# Serializer.net
KiCad netlist of a schematic drawn in Altium Designer
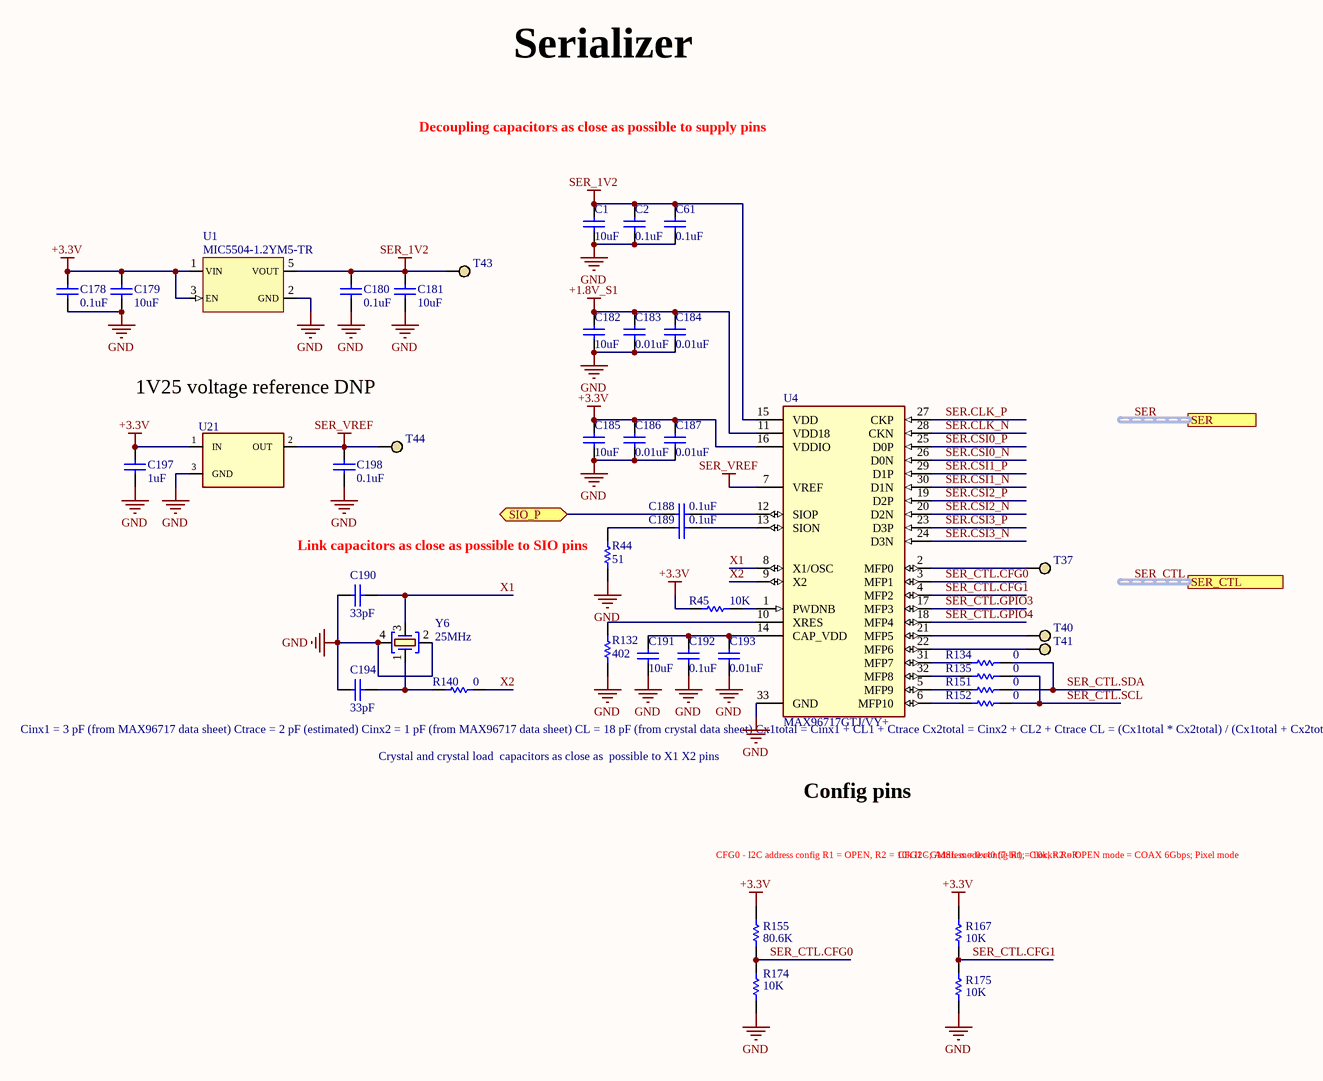
[diagram p0: Serializer.SchDoc]

(export (version "E")
  (design (tool "Eeschema 10.0.6"))
  (components
    (comp (ref "C1")
      (value "10uF")
      (footprint "CAPC1005X55USR")
      (description "CAP CER 10UF 10V X5R 0402")
      (fields
        (field (name "MANUFACTURER PART NUMBER") "CL05A106MP8NUB8")
        (field (name "MANUFACTURER") "Samsung Electro-Mechanics")
      )
      (libsource (lib "Radar FPGA RF") (part "CAP CER 10UF 10V X5R 0402"))
    )
    (comp (ref "C2")
      (value "0.1uF")
      (footprint "CAPC1005X55USR")
      (description "CAP CER 0.1UF 25V X5R 0402")
      (fields
        (field (name "MANUFACTURER PART NUMBER") "CL05A104KA5NNNC")
        (field (name "MANUFACTURER") "Samsung Electro-Mechanics")
      )
      (libsource (lib "Radar FPGA RF") (part "CAP CER 0.1UF 25V X5R 0402"))
    )
    (comp (ref "C61")
      (value "0.1uF")
      (footprint "CAPC1005X55USR")
      (description "CAP CER 0.1UF 25V X5R 0402")
      (fields
        (field (name "MANUFACTURER PART NUMBER") "CL05A104KA5NNNC")
        (field (name "MANUFACTURER") "Samsung Electro-Mechanics")
      )
      (libsource (lib "Radar FPGA RF") (part "CAP CER 0.1UF 25V X5R 0402"))
    )
    (comp (ref "C178")
      (value "0.1uF")
      (footprint "CAPC1005X55USR")
      (description "CAP CER 0.1UF 25V X7R 0402")
      (fields (field (name "MANUFACTURER") "AVX") (field (name "MANUFACTURER PART NUMBER") "04023C104KAT2A"))
      (libsource (lib "Signetik-passives") (part "0402C_0.1UF_25V_10%_X7R"))
    )
    (comp (ref "C179")
      (value "10uF")
      (footprint "CAPC1608X90N")
      (description "CAP CER 10UF 10V X5R 0603")
      (fields
        (field (name "MANUFACTURER") "Taiyo Yuden")
        (field (name "MANUFACTURER PART NUMBER") "LMK107BBJ106MALT")
      )
      (libsource (lib "Signetik-passives") (part "0603C_10UF_10V_20%_X5R"))
    )
    (comp (ref "C180")
      (value "0.1uF")
      (footprint "CAPC1005X55USR")
      (description "CAP CER 0.1UF 25V X7R 0402")
      (fields (field (name "MANUFACTURER") "AVX") (field (name "MANUFACTURER PART NUMBER") "04023C104KAT2A"))
      (libsource (lib "Signetik-passives") (part "0402C_0.1UF_25V_10%_X7R"))
    )
    (comp (ref "C181")
      (value "10uF")
      (footprint "CAPC1608X90N")
      (description "CAP CER 10UF 10V X5R 0603")
      (fields
        (field (name "MANUFACTURER") "Taiyo Yuden")
        (field (name "MANUFACTURER PART NUMBER") "LMK107BBJ106MALT")
      )
      (libsource (lib "Signetik-passives") (part "0603C_10UF_10V_20%_X5R"))
    )
    (comp (ref "C182")
      (value "10uF")
      (footprint "CAPC1005X55USR")
      (description "CAP CER 10UF 10V X5R 0402")
      (fields
        (field (name "MANUFACTURER PART NUMBER") "CL05A106MP8NUB8")
        (field (name "MANUFACTURER") "Samsung Electro-Mechanics")
      )
      (libsource (lib "Radar FPGA RF") (part "CAP CER 10UF 10V X5R 0402"))
    )
    (comp (ref "C183")
      (value "0.01uF")
      (footprint "CAPC1005X55USR")
      (description "CAP CER 10000PF 50V X7R 0402")
      (fields
        (field (name "MANUFACTURER PART NUMBER") "GCM155R71H103KA55D")
        (field (name "MANUFACTURER") "Murata Electronics")
      )
      (libsource (lib "Radar FPGA RF") (part "CAP CER 0.01uF 50V X7R 0402"))
    )
    (comp (ref "C184")
      (value "0.01uF")
      (footprint "CAPC1005X55USR")
      (description "CAP CER 10000PF 50V X7R 0402")
      (fields
        (field (name "MANUFACTURER PART NUMBER") "GCM155R71H103KA55D")
        (field (name "MANUFACTURER") "Murata Electronics")
      )
      (libsource (lib "Radar FPGA RF") (part "CAP CER 0.01uF 50V X7R 0402"))
    )
    (comp (ref "C185")
      (value "10uF")
      (footprint "CAPC1005X55USR")
      (description "CAP CER 10UF 10V X5R 0402")
      (fields
        (field (name "MANUFACTURER PART NUMBER") "CL05A106MP8NUB8")
        (field (name "MANUFACTURER") "Samsung Electro-Mechanics")
      )
      (libsource (lib "Radar FPGA RF") (part "CAP CER 10UF 10V X5R 0402"))
    )
    (comp (ref "C186")
      (value "0.01uF")
      (footprint "CAPC1005X55USR")
      (description "CAP CER 10000PF 50V X7R 0402")
      (fields
        (field (name "MANUFACTURER PART NUMBER") "GCM155R71H103KA55D")
        (field (name "MANUFACTURER") "Murata Electronics")
      )
      (libsource (lib "Radar FPGA RF") (part "CAP CER 0.01uF 50V X7R 0402"))
    )
    (comp (ref "C187")
      (value "0.01uF")
      (footprint "CAPC1005X55USR")
      (description "CAP CER 10000PF 50V X7R 0402")
      (fields
        (field (name "MANUFACTURER PART NUMBER") "GCM155R71H103KA55D")
        (field (name "MANUFACTURER") "Murata Electronics")
      )
      (libsource (lib "Radar FPGA RF") (part "CAP CER 0.01uF 50V X7R 0402"))
    )
    (comp (ref "C188")
      (value "0.1uF")
      (footprint "CAPC1005X55USR")
      (description "CAP CER 0.1UF 25V X5R 0402")
      (fields
        (field (name "MANUFACTURER PART NUMBER") "CL05A104KA5NNNC")
        (field (name "MANUFACTURER") "Samsung Electro-Mechanics")
      )
      (libsource (lib "Radar FPGA RF") (part "CAP CER 0.1UF 25V X5R 0402"))
    )
    (comp (ref "C189")
      (value "0.1uF")
      (footprint "CAPC1005X55USR")
      (description "CAP CER 0.1UF 25V X5R 0402")
      (fields
        (field (name "MANUFACTURER PART NUMBER") "CL05A104KA5NNNC")
        (field (name "MANUFACTURER") "Samsung Electro-Mechanics")
      )
      (libsource (lib "Radar FPGA RF") (part "CAP CER 0.1UF 25V X5R 0402"))
    )
    (comp (ref "C190")
      (value "33pF")
      (footprint "CAPC1005X55USR")
      (description "CAP CER 33PF 50V C0G/NP0 0402")
      (fields
        (field (name "MANUFACTURER PART NUMBER") "GRM1555C1H330JA01D")
        (field (name "MANUFACTURER") "Murata Electronics")
      )
      (libsource (lib "LL") (part "CAP CER 33PF 50V C0G/NP0 0402"))
    )
    (comp (ref "C191")
      (value "10uF")
      (footprint "CAPC1005X55USR")
      (description "CAP CER 10UF 10V X5R 0402")
      (fields
        (field (name "MANUFACTURER PART NUMBER") "CL05A106MP8NUB8")
        (field (name "MANUFACTURER") "Samsung Electro-Mechanics")
      )
      (libsource (lib "Radar FPGA RF") (part "CAP CER 10UF 10V X5R 0402"))
    )
    (comp (ref "C192")
      (value "0.1uF")
      (footprint "CAPC1005X55USR")
      (description "CAP CER 0.1UF 25V X5R 0402")
      (fields
        (field (name "MANUFACTURER PART NUMBER") "CL05A104KA5NNNC")
        (field (name "MANUFACTURER") "Samsung Electro-Mechanics")
      )
      (libsource (lib "Radar FPGA RF") (part "CAP CER 0.1UF 25V X5R 0402"))
    )
    (comp (ref "C193")
      (value "0.01uF")
      (footprint "CAPC1005X55USR")
      (description "CAP CER 10000PF 50V X7R 0402")
      (fields
        (field (name "MANUFACTURER PART NUMBER") "GCM155R71H103KA55D")
        (field (name "MANUFACTURER") "Murata Electronics")
      )
      (libsource (lib "Radar FPGA RF") (part "CAP CER 0.01uF 50V X7R 0402"))
    )
    (comp (ref "C194")
      (value "33pF")
      (footprint "CAPC1005X55USR")
      (description "CAP CER 33PF 50V C0G/NP0 0402")
      (fields
        (field (name "MANUFACTURER PART NUMBER") "GRM1555C1H330JA01D")
        (field (name "MANUFACTURER") "Murata Electronics")
      )
      (libsource (lib "LL") (part "CAP CER 33PF 50V C0G/NP0 0402"))
    )
    (comp (ref "C197")
      (value "1uF")
      (footprint "CAPC1005X55USR")
      (description "CAP CER 1UF 10V X5R 0402")
      (fields
        (field (name "MANUFACTURER PART NUMBER") "CL05A105MP5NNNC")
        (field (name "MANUFACTURER") "Samsung Electro-Mechanics")
      )
      (libsource (lib "LL") (part "CAP CER 1UF 10V X5R 0402"))
    )
    (comp (ref "C198")
      (value "0.1uF")
      (footprint "CAPC1005X55USR")
      (description "CAP CER 0.1UF 25V X7R 0402")
      (fields (field (name "MANUFACTURER") "AVX") (field (name "MANUFACTURER PART NUMBER") "04023C104KAT2A"))
      (libsource (lib "Signetik-passives") (part "0402C_0.1UF_25V_10%_X7R"))
    )
    (comp (ref "R44")
      (value "51")
      (footprint "RESC1005X40USR")
      (description "RES 51 OHM 1% 1/16W 0402")
      (fields
        (field (name "MANUFACTURER PART NUMBER") "RC0402FR-0751RL")
        (field (name "MANUFACTURER") "YAGEO")
      )
      (libsource (lib "LL") (part "RES 51 OHM 1% 1/16W 0402"))
    )
    (comp (ref "R45")
      (value "10K")
      (footprint "RESC1005X40USR")
      (description "RES 10K OHM 1% 1/16W 0402")
      (fields
        (field (name "MANUFACTURER") "YAGEO")
        (field (name "MANUFACTURER PART NUMBER") "RC0402FR-0710KL")
      )
      (libsource (lib "Radar FPGA RF") (part "RES 10K OHM 1% 1/16W 0402"))
    )
    (comp (ref "R132")
      (value "402")
      (footprint "RESC1005X40USR")
      (description "RES 402 OHM 1% 1/16W 0402")
      (fields
        (field (name "MANUFACTURER PART NUMBER") "RC0402FR-07402RL")
        (field (name "MANUFACTURER") "YAGEO")
      )
      (libsource (lib "LL") (part "RES 402 OHM 1% 1/16W 0402"))
    )
    (comp (ref "R134")
      (value "0")
      (footprint "RESC1005X40USR")
      (description "RES 0 OHM JUMPER 1/16W 0402")
      (fields
        (field (name "MANUFACTURER") "Yageo")
        (field (name "MANUFACTURER PART NUMBER") "RC0402JR-070RL")
      )
      (libsource (lib "Radar FPGA RF") (part "RES 0 OHM JUMPER 1/16W 0402"))
    )
    (comp (ref "R135")
      (value "0")
      (footprint "RESC1005X40USR")
      (description "RES 0 OHM JUMPER 1/16W 0402")
      (fields
        (field (name "MANUFACTURER") "Yageo")
        (field (name "MANUFACTURER PART NUMBER") "RC0402JR-070RL")
      )
      (libsource (lib "Radar FPGA RF") (part "RES 0 OHM JUMPER 1/16W 0402"))
    )
    (comp (ref "R140")
      (value "0")
      (footprint "RESC1005X40USR")
      (description "RES 0 OHM JUMPER 1/16W 0402")
      (fields
        (field (name "MANUFACTURER") "Yageo")
        (field (name "MANUFACTURER PART NUMBER") "RC0402JR-070RL")
      )
      (libsource (lib "Radar FPGA RF") (part "RES 0 OHM JUMPER 1/16W 0402"))
    )
    (comp (ref "R151")
      (value "0")
      (footprint "RESC1005X40USR")
      (description "RES 0 OHM JUMPER 1/16W 0402")
      (fields
        (field (name "MANUFACTURER") "Yageo")
        (field (name "MANUFACTURER PART NUMBER") "RC0402JR-070RL")
      )
      (libsource (lib "Radar FPGA RF") (part "RES 0 OHM JUMPER 1/16W 0402"))
    )
    (comp (ref "R152")
      (value "0")
      (footprint "RESC1005X40USR")
      (description "RES 0 OHM JUMPER 1/16W 0402")
      (fields
        (field (name "MANUFACTURER") "Yageo")
        (field (name "MANUFACTURER PART NUMBER") "RC0402JR-070RL")
      )
      (libsource (lib "Radar FPGA RF") (part "RES 0 OHM JUMPER 1/16W 0402"))
    )
    (comp (ref "R155")
      (value "80.6K")
      (footprint "RESC1005X40USR")
      (description "RES 80.6K OHM 1% 1/16W 0402")
      (fields
        (field (name "MANUFACTURER") "YAGEO")
        (field (name "MANUFACTURER PART NUMBER") "RC0402FR-0780K6L")
      )
      (libsource (lib "LL") (part "RES 80.6K OHM 1% 1/16W 0402"))
    )
    (comp (ref "R167")
      (value "10K")
      (footprint "RESC1005X40USR")
      (description "RES 10K OHM 1% 1/16W 0402")
      (fields
        (field (name "MANUFACTURER") "YAGEO")
        (field (name "MANUFACTURER PART NUMBER") "RC0402FR-0710KL")
      )
      (libsource (lib "LL") (part "RES 10K OHM 1% 1/16W 0402"))
    )
    (comp (ref "R174")
      (value "10K")
      (footprint "RESC1005X40USR")
      (description "RES 10K OHM 1% 1/16W 0402")
      (fields
        (field (name "MANUFACTURER") "YAGEO")
        (field (name "MANUFACTURER PART NUMBER") "RC0402FR-0710KL")
      )
      (libsource (lib "LL") (part "RES 10K OHM 1% 1/16W 0402"))
    )
    (comp (ref "R175")
      (value "10K")
      (footprint "RESC1005X40USR")
      (description "RES 10K OHM 1% 1/16W 0402")
      (fields
        (field (name "MANUFACTURER") "YAGEO")
        (field (name "MANUFACTURER PART NUMBER") "RC0402FR-0710KL")
      )
      (libsource (lib "LL") (part "RES 10K OHM 1% 1/16W 0402"))
    )
    (comp (ref "T37")
      (value "TP_S")
      (footprint "TP 1mm")
      (description "test point")
      (libsource (lib "Radar FPGA RF") (part "Test point PAD"))
    )
    (comp (ref "T40")
      (value "TP_S")
      (footprint "TP 1mm")
      (description "test point")
      (libsource (lib "Radar FPGA RF") (part "Test point PAD"))
    )
    (comp (ref "T41")
      (value "TP_S")
      (footprint "TP 1mm")
      (description "test point")
      (libsource (lib "Radar FPGA RF") (part "Test point PAD"))
    )
    (comp (ref "T43")
      (value "TP_S")
      (footprint "TP 1mm")
      (description "test point")
      (libsource (lib "Radar FPGA RF") (part "Test point PAD"))
    )
    (comp (ref "T44")
      (value "TP_S")
      (footprint "TP 1mm")
      (description "test point")
      (libsource (lib "Radar FPGA RF") (part "Test point PAD"))
    )
    (comp (ref "U1")
      (value "MIC5504-1.2YM5-TR")
      (footprint "SOT23-5")
      (description "IC REG LINEAR 1.2V 300MA SOT23-5")
      (fields (field (name "MANUFACTURER") "Microchip"))
      (libsource (lib "cvlib") (part "MIC550x"))
    )
    (comp (ref "U4")
      (value "MAX96717GTJ/VY+")
      (footprint "QFN50P500X500X80-33N")
      (description "GMSL2 Compact Serializer")
      (fields (field (name "MANUFACTURER") "Maxim"))
      (libsource (lib "LL") (part "MAX96717GTJ/VY+"))
    )
    (comp (ref "U21")
      (value "REF3012AIDBZT")
      (footprint "SOT-23")
      (description "1.25V 50ppm/Degrees C, 50uA in SOT23-3 Series (Bandgap) Voltage Reference 3-SOT-23 -40 to 125")
      (fields (field (name "MANUFACTURER") "Texas Instruments") (field (name "TOLERANCE") "0.2%"))
      (libsource (lib "LL") (part "REF3012AIDBZT"))
    )
    (comp (ref "Y6")
      (value "25MHz")
      (footprint "XTAL_ABM8G_3225")
      (description "Crystal 25MHz ±20ppm (Tol) ±30ppm (Stability) 18pF FUND 60Ohm 4-Pin Ultra Mini-CSMD T/R")
      (fields
        (field (name "MANUFACTURER") "Abracon")
        (field (name "MANUFACTURER PART NUMBER") "ABM8G-25.000MHZ-18-D2Y-T3")
      )
      (libsource (lib "LL") (part "XTAL_ABM8G-25.000MHZ-18-D2Y-T3"))
    )
  )
  (nets
    (net (code "3") (name "+1.8V_S1") (class "Default")
      (node (ref "C182") (pin "2") (pinfunction "2_2") (pintype "passive"))
      (node (ref "C183") (pin "2") (pinfunction "2_2") (pintype "passive"))
      (node (ref "C184") (pin "2") (pinfunction "2_2") (pintype "passive"))
      (node (ref "U4") (pin "11") (pinfunction "VDD18_11") (pintype "power_in"))
    )
    (net (code "4") (name "+3.3V") (class "Default")
      (node (ref "C178") (pin "2") (pinfunction "2_2") (pintype "passive"))
      (node (ref "C179") (pin "2") (pinfunction "2_2") (pintype "passive"))
      (node (ref "C185") (pin "2") (pinfunction "2_2") (pintype "passive"))
      (node (ref "C186") (pin "2") (pinfunction "2_2") (pintype "passive"))
      (node (ref "C187") (pin "2") (pinfunction "2_2") (pintype "passive"))
      (node (ref "C197") (pin "2") (pinfunction "2_2") (pintype "passive"))
      (node (ref "R155") (pin "2") (pinfunction "2_2") (pintype "passive"))
      (node (ref "R167") (pin "2") (pinfunction "2_2") (pintype "passive"))
      (node (ref "R45") (pin "2") (pinfunction "2_2") (pintype "passive"))
      (node (ref "U1") (pin "1") (pinfunction "VIN_1") (pintype "power_in"))
      (node (ref "U1") (pin "3") (pinfunction "EN_3") (pintype "input"))
      (node (ref "U21") (pin "1") (pinfunction "IN_1") (pintype "power_in"))
      (node (ref "U4") (pin "16") (pinfunction "VDDIO_16") (pintype "power_in"))
    )
    (net (code "5") (name "/SER.CLK_N") (class "Default")
      (node (ref "U4") (pin "28") (pinfunction "CKN_28") (pintype "input"))
    )
    (net (code "6") (name "/SER.CLK_P") (class "Default")
      (node (ref "U4") (pin "27") (pinfunction "CKP_27") (pintype "input"))
    )
    (net (code "7") (name "/SER.CSI0_N") (class "Default")
      (node (ref "U4") (pin "26") (pinfunction "D0N_26") (pintype "input"))
    )
    (net (code "8") (name "/SER.CSI0_P") (class "Default")
      (node (ref "U4") (pin "25") (pinfunction "D0P_25") (pintype "input"))
    )
    (net (code "9") (name "/SER.CSI1_N") (class "Default")
      (node (ref "U4") (pin "30") (pinfunction "D1N_30") (pintype "input"))
    )
    (net (code "10") (name "/SER.CSI1_P") (class "Default")
      (node (ref "U4") (pin "29") (pinfunction "D1P_29") (pintype "input"))
    )
    (net (code "11") (name "/SER.CSI2_N") (class "Default")
      (node (ref "U4") (pin "20") (pinfunction "D2N_20") (pintype "input"))
    )
    (net (code "12") (name "/SER.CSI2_P") (class "Default")
      (node (ref "U4") (pin "19") (pinfunction "D2P_19") (pintype "input"))
    )
    (net (code "13") (name "/SER.CSI3_N") (class "Default")
      (node (ref "U4") (pin "24") (pinfunction "D3N_24") (pintype "input"))
    )
    (net (code "14") (name "/SER.CSI3_P") (class "Default")
      (node (ref "U4") (pin "23") (pinfunction "D3P_23") (pintype "input"))
    )
    (net (code "15") (name "/SER_CTL.CFG0") (class "Default")
      (node (ref "R155") (pin "1") (pinfunction "1_1") (pintype "passive"))
      (node (ref "R174") (pin "2") (pinfunction "2_2") (pintype "passive"))
      (node (ref "U4") (pin "3") (pinfunction "MFP1_3") (pintype "bidirectional"))
    )
    (net (code "16") (name "/SER_CTL.CFG1") (class "Default")
      (node (ref "R167") (pin "1") (pinfunction "1_1") (pintype "passive"))
      (node (ref "R175") (pin "2") (pinfunction "2_2") (pintype "passive"))
      (node (ref "U4") (pin "4") (pinfunction "MFP2_4") (pintype "bidirectional"))
    )
    (net (code "17") (name "/SER_CTL.GPIO3") (class "Default")
      (node (ref "U4") (pin "17") (pinfunction "MFP3_17") (pintype "bidirectional"))
    )
    (net (code "18") (name "/SER_CTL.GPIO4") (class "Default")
      (node (ref "U4") (pin "18") (pinfunction "MFP4_18") (pintype "bidirectional"))
    )
    (net (code "19") (name "/SER_CTL.SCL") (class "Default")
      (node (ref "R135") (pin "2") (pinfunction "2_2") (pintype "passive"))
      (node (ref "R152") (pin "2") (pinfunction "2_2") (pintype "passive"))
    )
    (net (code "20") (name "/SER_CTL.SDA") (class "Default")
      (node (ref "R134") (pin "2") (pinfunction "2_2") (pintype "passive"))
      (node (ref "R151") (pin "2") (pinfunction "2_2") (pintype "passive"))
    )
    (net (code "21") (name "/SIO_P") (class "Default")
      (node (ref "C188") (pin "1") (pinfunction "1_1") (pintype "passive"))
    )
    (net (code "22") (name "/X1") (class "Default")
      (node (ref "C190") (pin "2") (pinfunction "2_2") (pintype "passive"))
      (node (ref "U4") (pin "8") (pinfunction "X1/OSC_8") (pintype "bidirectional"))
      (node (ref "Y6") (pin "3") (pinfunction "3_3") (pintype "passive"))
    )
    (net (code "23") (name "/X2") (class "Default")
      (node (ref "R140") (pin "2") (pinfunction "2_2") (pintype "passive"))
      (node (ref "U4") (pin "9") (pinfunction "X2_9") (pintype "bidirectional"))
    )
    (net (code "26") (name "GND") (class "Default")
      (node (ref "C1") (pin "1") (pinfunction "1_1") (pintype "passive"))
      (node (ref "C178") (pin "1") (pinfunction "1_1") (pintype "passive"))
      (node (ref "C179") (pin "1") (pinfunction "1_1") (pintype "passive"))
      (node (ref "C180") (pin "1") (pinfunction "1_1") (pintype "passive"))
      (node (ref "C181") (pin "1") (pinfunction "1_1") (pintype "passive"))
      (node (ref "C182") (pin "1") (pinfunction "1_1") (pintype "passive"))
      (node (ref "C183") (pin "1") (pinfunction "1_1") (pintype "passive"))
      (node (ref "C184") (pin "1") (pinfunction "1_1") (pintype "passive"))
      (node (ref "C185") (pin "1") (pinfunction "1_1") (pintype "passive"))
      (node (ref "C186") (pin "1") (pinfunction "1_1") (pintype "passive"))
      (node (ref "C187") (pin "1") (pinfunction "1_1") (pintype "passive"))
      (node (ref "C190") (pin "1") (pinfunction "1_1") (pintype "passive"))
      (node (ref "C191") (pin "1") (pinfunction "1_1") (pintype "passive"))
      (node (ref "C192") (pin "2") (pinfunction "2_2") (pintype "passive"))
      (node (ref "C193") (pin "1") (pinfunction "1_1") (pintype "passive"))
      (node (ref "C194") (pin "1") (pinfunction "1_1") (pintype "passive"))
      (node (ref "C197") (pin "1") (pinfunction "1_1") (pintype "passive"))
      (node (ref "C198") (pin "1") (pinfunction "1_1") (pintype "passive"))
      (node (ref "C2") (pin "2") (pinfunction "2_2") (pintype "passive"))
      (node (ref "C61") (pin "2") (pinfunction "2_2") (pintype "passive"))
      (node (ref "R132") (pin "1") (pinfunction "1_1") (pintype "passive"))
      (node (ref "R174") (pin "1") (pinfunction "1_1") (pintype "passive"))
      (node (ref "R175") (pin "1") (pinfunction "1_1") (pintype "passive"))
      (node (ref "R44") (pin "1") (pinfunction "1_1") (pintype "passive"))
      (node (ref "U1") (pin "2") (pinfunction "GND_2") (pintype "power_in"))
      (node (ref "U21") (pin "3") (pinfunction "GND_3") (pintype "passive"))
      (node (ref "U4") (pin "33") (pinfunction "GND_33") (pintype "power_in"))
      (node (ref "Y6") (pin "2") (pinfunction "SH_2") (pintype "passive"))
      (node (ref "Y6") (pin "4") (pinfunction "SH_4") (pintype "passive"))
    )
    (net (code "27") (name "Net-(C189-Pad1)") (class "Default")
      (node (ref "C189") (pin "1") (pinfunction "1_1") (pintype "passive"))
      (node (ref "R44") (pin "2") (pinfunction "2_2") (pintype "passive"))
    )
    (net (code "28") (name "Net-(C194-Pad2)") (class "Default")
      (node (ref "C194") (pin "2") (pinfunction "2_2") (pintype "passive"))
      (node (ref "R140") (pin "1") (pinfunction "1_1") (pintype "passive"))
      (node (ref "Y6") (pin "1") (pinfunction "1_1") (pintype "passive"))
    )
    (net (code "29") (name "Net-(U4-CAP_VDD)") (class "Default")
      (node (ref "C191") (pin "2") (pinfunction "2_2") (pintype "passive"))
      (node (ref "C192") (pin "1") (pinfunction "1_1") (pintype "passive"))
      (node (ref "C193") (pin "2") (pinfunction "2_2") (pintype "passive"))
      (node (ref "U4") (pin "14") (pinfunction "CAP_VDD_14") (pintype "power_in"))
    )
    (net (code "30") (name "Net-(U4-MFP0)") (class "Default")
      (node (ref "T37") (pin "1") (pintype "passive"))
      (node (ref "U4") (pin "2") (pinfunction "MFP0_2") (pintype "bidirectional"))
    )
    (net (code "31") (name "Net-(U4-MFP5)") (class "Default")
      (node (ref "T40") (pin "1") (pintype "passive"))
      (node (ref "U4") (pin "21") (pinfunction "MFP5_21") (pintype "bidirectional"))
    )
    (net (code "32") (name "Net-(U4-MFP6)") (class "Default")
      (node (ref "T41") (pin "1") (pintype "passive"))
      (node (ref "U4") (pin "22") (pinfunction "MFP6_22") (pintype "bidirectional"))
    )
    (net (code "33") (name "Net-(U4-MFP7)") (class "Default")
      (node (ref "R134") (pin "1") (pinfunction "1_1") (pintype "passive"))
      (node (ref "U4") (pin "31") (pinfunction "MFP7_31") (pintype "bidirectional"))
    )
    (net (code "34") (name "Net-(U4-MFP8)") (class "Default")
      (node (ref "R135") (pin "1") (pinfunction "1_1") (pintype "passive"))
      (node (ref "U4") (pin "32") (pinfunction "MFP8_32") (pintype "bidirectional"))
    )
    (net (code "35") (name "Net-(U4-MFP9)") (class "Default")
      (node (ref "R151") (pin "1") (pinfunction "1_1") (pintype "passive"))
      (node (ref "U4") (pin "5") (pinfunction "MFP9_5") (pintype "bidirectional"))
    )
    (net (code "36") (name "Net-(U4-MFP10)") (class "Default")
      (node (ref "R152") (pin "1") (pinfunction "1_1") (pintype "passive"))
      (node (ref "U4") (pin "6") (pinfunction "MFP10_6") (pintype "bidirectional"))
    )
    (net (code "37") (name "Net-(U4-PWDNB)") (class "Default")
      (node (ref "R45") (pin "1") (pinfunction "1_1") (pintype "passive"))
      (node (ref "U4") (pin "1") (pinfunction "PWDNB_1") (pintype "input"))
    )
    (net (code "38") (name "Net-(U4-SION)") (class "Default")
      (node (ref "C189") (pin "2") (pinfunction "2_2") (pintype "passive"))
      (node (ref "U4") (pin "13") (pinfunction "SION_13") (pintype "bidirectional"))
    )
    (net (code "39") (name "Net-(U4-SIOP)") (class "Default")
      (node (ref "C188") (pin "2") (pinfunction "2_2") (pintype "passive"))
      (node (ref "U4") (pin "12") (pinfunction "SIOP_12") (pintype "bidirectional"))
    )
    (net (code "40") (name "Net-(U4-XRES)") (class "Default")
      (node (ref "R132") (pin "2") (pinfunction "2_2") (pintype "passive"))
      (node (ref "U4") (pin "10") (pinfunction "XRES_10") (pintype "passive"))
    )
    (net (code "41") (name "SER_1V2") (class "Default")
      (node (ref "C1") (pin "2") (pinfunction "2_2") (pintype "passive"))
      (node (ref "C180") (pin "2") (pinfunction "2_2") (pintype "passive"))
      (node (ref "C181") (pin "2") (pinfunction "2_2") (pintype "passive"))
      (node (ref "C2") (pin "1") (pinfunction "1_1") (pintype "passive"))
      (node (ref "C61") (pin "1") (pinfunction "1_1") (pintype "passive"))
      (node (ref "T43") (pin "1") (pintype "passive"))
      (node (ref "U1") (pin "5") (pinfunction "VOUT_5") (pintype "power_in"))
      (node (ref "U4") (pin "15") (pinfunction "VDD_15") (pintype "power_in"))
    )
    (net (code "42") (name "SER_VREF") (class "Default")
      (node (ref "C198") (pin "2") (pinfunction "2_2") (pintype "passive"))
      (node (ref "T44") (pin "1") (pintype "passive"))
      (node (ref "U21") (pin "2") (pinfunction "OUT_2") (pintype "power_in"))
      (node (ref "U4") (pin "7") (pinfunction "VREF_7") (pintype "power_in"))
    )
  )
)
